# esp12e-test.net
KiCad netlist of a schematic drawn in EAGLE
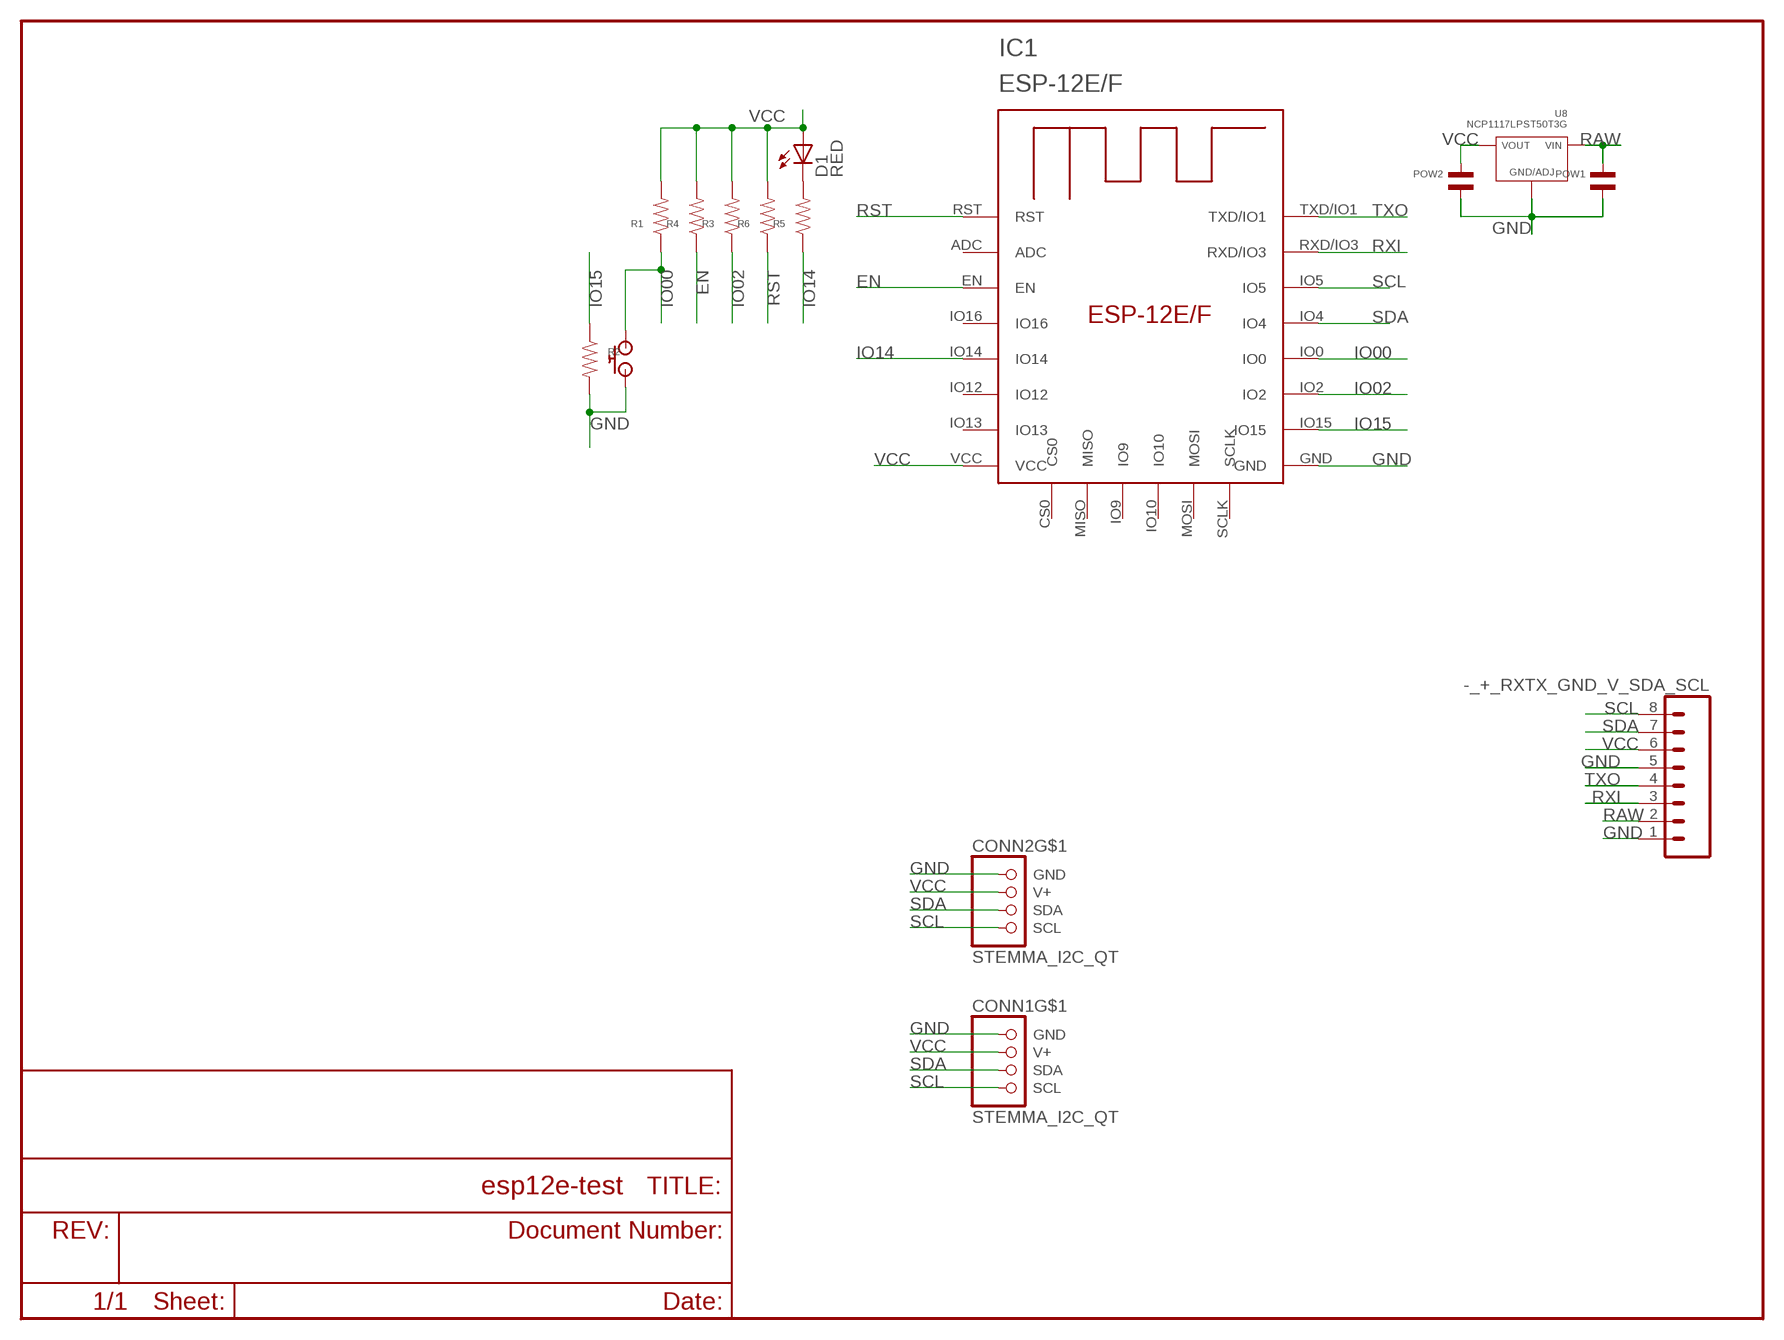
[diagram p0: schematic, sheet 1]

(export (version "E")
  (design (tool "Eeschema 10.0.6"))
  (components
    (comp (ref "-_+_RXTX_GND_V_SDA_SCL")
      (value "MF-CON-2.54mm-01x08")
      (footprint "eagle-import:1X08")
      (libsource (lib "eagle-import") (part "M081X08"))
    )
    (comp (ref "CONN1")
      (value "STEMMA_I2C_QT")
      (footprint "eagle-import:JST_SH4")
      (libsource (lib "eagle-import") (part "STEMMA_I2C_QT"))
    )
    (comp (ref "CONN2")
      (value "STEMMA_I2C_QT")
      (footprint "eagle-import:JST_SH4")
      (libsource (lib "eagle-import") (part "STEMMA_I2C_QT"))
    )
    (comp (ref "D1")
      (value "RED")
      (footprint "eagle-import:LED-0603")
      (libsource (lib "eagle-import") (part "LED-RED0603"))
    )
    (comp (ref "IC1")
      (value "ESP-12E/F")
      (footprint "eagle-import:ESP-12E")
      (libsource (lib "eagle-import") (part "ESP-12E/F"))
    )
    (comp (ref "POW1")
      (value "CAPACITOR_NP_1210")
      (footprint "eagle-import:C1210")
      (libsource (lib "eagle-import") (part "CAPACITOR_NP_1210"))
    )
    (comp (ref "POW2")
      (value "CAPACITOR_NP_1210")
      (footprint "eagle-import:C1210")
      (libsource (lib "eagle-import") (part "CAPACITOR_NP_1210"))
    )
    (comp (ref "R1")
      (value "RESISTOR_0603")
      (footprint "eagle-import:R0603")
      (libsource (lib "eagle-import") (part "RESISTOR_0603"))
    )
    (comp (ref "R2")
      (value "RESISTOR_0603")
      (footprint "eagle-import:R0603")
      (libsource (lib "eagle-import") (part "RESISTOR_0603"))
    )
    (comp (ref "R3")
      (value "RESISTOR_0603")
      (footprint "eagle-import:R0603")
      (libsource (lib "eagle-import") (part "RESISTOR_0603"))
    )
    (comp (ref "R4")
      (value "RESISTOR_0603")
      (footprint "eagle-import:R0603")
      (libsource (lib "eagle-import") (part "RESISTOR_0603"))
    )
    (comp (ref "R5")
      (value "RESISTOR_0603")
      (footprint "eagle-import:R0603")
      (libsource (lib "eagle-import") (part "RESISTOR_0603"))
    )
    (comp (ref "R6")
      (value "RESISTOR_0603")
      (footprint "eagle-import:R0603")
      (libsource (lib "eagle-import") (part "RESISTOR_0603"))
    )
    (comp (ref "U$1")
      (value "AMAZON_BUTTON")
      (footprint "eagle-import:AMAZON_BUTTON")
      (libsource (lib "eagle-import") (part "AMAZON_BUTTON"))
    )
    (comp (ref "U8")
      (value "NCP1117LPST50T3G")
      (footprint "eagle-import:SOT-223-3")
      (fields (field (name "HOUSEPART") "NO"))
      (libsource (lib "eagle-import") (part "NCP1117LPST50T3G"))
    )
  )
  (nets
    (net (code "1") (name "/EN") (class "Default")
      (node (ref "IC1") (pin "EN") (pinfunction "EN_EN") (pintype "bidirectional"))
      (node (ref "R4") (pin "P$1") (pinfunction "P$1_P$1") (pintype "passive"))
    )
    (net (code "2") (name "/GND") (class "Default")
      (node (ref "-_+_RXTX_GND_V_SDA_SCL") (pin "1") (pinfunction "1_1") (pintype "passive"))
      (node (ref "-_+_RXTX_GND_V_SDA_SCL") (pin "5") (pinfunction "5_5") (pintype "passive"))
      (node (ref "CONN1") (pin "1") (pinfunction "GND_1") (pintype "passive"))
      (node (ref "CONN2") (pin "1") (pinfunction "GND_1") (pintype "passive"))
      (node (ref "IC1") (pin "GND") (pinfunction "GND_GND") (pintype "power_in"))
      (node (ref "POW1") (pin "P$2") (pinfunction "P$2_P$2") (pintype "passive"))
      (node (ref "POW2") (pin "P$2") (pinfunction "P$2_P$2") (pintype "passive"))
      (node (ref "R2") (pin "P$2") (pinfunction "P$2_P$2") (pintype "passive"))
      (node (ref "U$1") (pin "2") (pinfunction "P$2_2") (pintype "bidirectional"))
      (node (ref "U$1") (pin "3") (pinfunction "P$2_3") (pintype "bidirectional"))
      (node (ref "U8") (pin "P$2") (pinfunction "GND/ADJ_P$2") (pintype "bidirectional"))
    )
    (net (code "3") (name "/IO00") (class "Default")
      (node (ref "IC1") (pin "IO0") (pinfunction "IO0_IO0") (pintype "bidirectional"))
      (node (ref "R1") (pin "P$1") (pinfunction "P$1_P$1") (pintype "passive"))
      (node (ref "U$1") (pin "1") (pinfunction "P$1_1") (pintype "bidirectional"))
      (node (ref "U$1") (pin "4") (pinfunction "P$1_4") (pintype "bidirectional"))
    )
    (net (code "4") (name "/IO02") (class "Default")
      (node (ref "IC1") (pin "IO2") (pinfunction "IO2_IO2") (pintype "bidirectional"))
      (node (ref "R3") (pin "P$1") (pinfunction "P$1_P$1") (pintype "passive"))
    )
    (net (code "5") (name "/IO14") (class "Default")
      (node (ref "IC1") (pin "IO14") (pinfunction "IO14_IO14") (pintype "bidirectional"))
      (node (ref "R5") (pin "P$1") (pinfunction "P$1_P$1") (pintype "passive"))
    )
    (net (code "6") (name "/IO15") (class "Default")
      (node (ref "IC1") (pin "IO15") (pinfunction "IO15_IO15") (pintype "bidirectional"))
      (node (ref "R2") (pin "P$1") (pinfunction "P$1_P$1") (pintype "passive"))
    )
    (net (code "7") (name "/RAW") (class "Default")
      (node (ref "-_+_RXTX_GND_V_SDA_SCL") (pin "2") (pinfunction "2_2") (pintype "passive"))
      (node (ref "POW1") (pin "P$1") (pinfunction "P$1_P$1") (pintype "passive"))
      (node (ref "U8") (pin "P$4") (pinfunction "VIN_P$4") (pintype "bidirectional"))
    )
    (net (code "8") (name "/RST") (class "Default")
      (node (ref "IC1") (pin "RST") (pinfunction "RST_RST") (pintype "input"))
      (node (ref "R6") (pin "P$1") (pinfunction "P$1_P$1") (pintype "passive"))
    )
    (net (code "9") (name "/RXI") (class "Default")
      (node (ref "-_+_RXTX_GND_V_SDA_SCL") (pin "3") (pinfunction "3_3") (pintype "passive"))
      (node (ref "IC1") (pin "RXD/IO3") (pinfunction "RXD/IO3_RXD/IO3") (pintype "bidirectional"))
    )
    (net (code "10") (name "/SCL") (class "Default")
      (node (ref "-_+_RXTX_GND_V_SDA_SCL") (pin "8") (pinfunction "8_8") (pintype "passive"))
      (node (ref "CONN1") (pin "4") (pinfunction "SCL_4") (pintype "passive"))
      (node (ref "CONN2") (pin "4") (pinfunction "SCL_4") (pintype "passive"))
      (node (ref "IC1") (pin "IO5") (pinfunction "IO5_IO5") (pintype "bidirectional"))
    )
    (net (code "11") (name "/SDA") (class "Default")
      (node (ref "-_+_RXTX_GND_V_SDA_SCL") (pin "7") (pinfunction "7_7") (pintype "passive"))
      (node (ref "CONN1") (pin "3") (pinfunction "SDA_3") (pintype "passive"))
      (node (ref "CONN2") (pin "3") (pinfunction "SDA_3") (pintype "passive"))
      (node (ref "IC1") (pin "IO4") (pinfunction "IO4_IO4") (pintype "bidirectional"))
    )
    (net (code "12") (name "/TXO") (class "Default")
      (node (ref "-_+_RXTX_GND_V_SDA_SCL") (pin "4") (pinfunction "4_4") (pintype "passive"))
      (node (ref "IC1") (pin "TXD/IO1") (pinfunction "TXD/IO1_TXD/IO1") (pintype "bidirectional"))
    )
    (net (code "13") (name "/VCC") (class "Default")
      (node (ref "-_+_RXTX_GND_V_SDA_SCL") (pin "6") (pinfunction "6_6") (pintype "passive"))
      (node (ref "CONN1") (pin "2") (pinfunction "V+_2") (pintype "passive"))
      (node (ref "CONN2") (pin "2") (pinfunction "V+_2") (pintype "passive"))
      (node (ref "D1") (pin "A") (pinfunction "A_A") (pintype "passive"))
      (node (ref "IC1") (pin "VCC") (pinfunction "VCC_VCC") (pintype "power_in"))
      (node (ref "POW2") (pin "P$1") (pinfunction "P$1_P$1") (pintype "passive"))
      (node (ref "R1") (pin "P$2") (pinfunction "P$2_P$2") (pintype "passive"))
      (node (ref "R3") (pin "P$2") (pinfunction "P$2_P$2") (pintype "passive"))
      (node (ref "R4") (pin "P$2") (pinfunction "P$2_P$2") (pintype "passive"))
      (node (ref "R6") (pin "P$2") (pinfunction "P$2_P$2") (pintype "passive"))
      (node (ref "U8") (pin "P$1") (pinfunction "VOUT_P$1") (pintype "bidirectional"))
      (node (ref "U8") (pin "P$3") (pinfunction "VOUT_P$3") (pintype "bidirectional"))
    )
    (net (code "14") (name "Net-(D1-PadC)") (class "Default")
      (node (ref "D1") (pin "C") (pinfunction "C_C") (pintype "passive"))
      (node (ref "R5") (pin "P$2") (pinfunction "P$2_P$2") (pintype "passive"))
    )
    (net (code "15") (name "unconnected-(IC1-PadADC)") (class "Default")
      (node (ref "IC1") (pin "ADC") (pinfunction "ADC_ADC") (pintype "bidirectional"))
    )
    (net (code "16") (name "unconnected-(IC1-PadCS0)") (class "Default")
      (node (ref "IC1") (pin "CS0") (pinfunction "CS0_CS0") (pintype "bidirectional"))
    )
    (net (code "17") (name "unconnected-(IC1-PadIO9)") (class "Default")
      (node (ref "IC1") (pin "IO9") (pinfunction "IO9_IO9") (pintype "bidirectional"))
    )
    (net (code "18") (name "unconnected-(IC1-PadIO10)") (class "Default")
      (node (ref "IC1") (pin "IO10") (pinfunction "IO10_IO10") (pintype "bidirectional"))
    )
    (net (code "19") (name "unconnected-(IC1-PadIO12)") (class "Default")
      (node (ref "IC1") (pin "IO12") (pinfunction "IO12_IO12") (pintype "bidirectional"))
    )
    (net (code "20") (name "unconnected-(IC1-PadIO13)") (class "Default")
      (node (ref "IC1") (pin "IO13") (pinfunction "IO13_IO13") (pintype "bidirectional"))
    )
    (net (code "21") (name "unconnected-(IC1-PadIO16)") (class "Default")
      (node (ref "IC1") (pin "IO16") (pinfunction "IO16_IO16") (pintype "bidirectional"))
    )
    (net (code "22") (name "unconnected-(IC1-PadMISO)") (class "Default")
      (node (ref "IC1") (pin "MISO") (pinfunction "MISO_MISO") (pintype "bidirectional"))
    )
    (net (code "23") (name "unconnected-(IC1-PadMOSI)") (class "Default")
      (node (ref "IC1") (pin "MOSI") (pinfunction "MOSI_MOSI") (pintype "bidirectional"))
    )
    (net (code "24") (name "unconnected-(IC1-PadSCLK)") (class "Default")
      (node (ref "IC1") (pin "SCLK") (pinfunction "SCLK_SCLK") (pintype "bidirectional"))
    )
  )
)
